# meld_all_non_inv.net
KiCad netlist of a schematic drawn in EAGLE
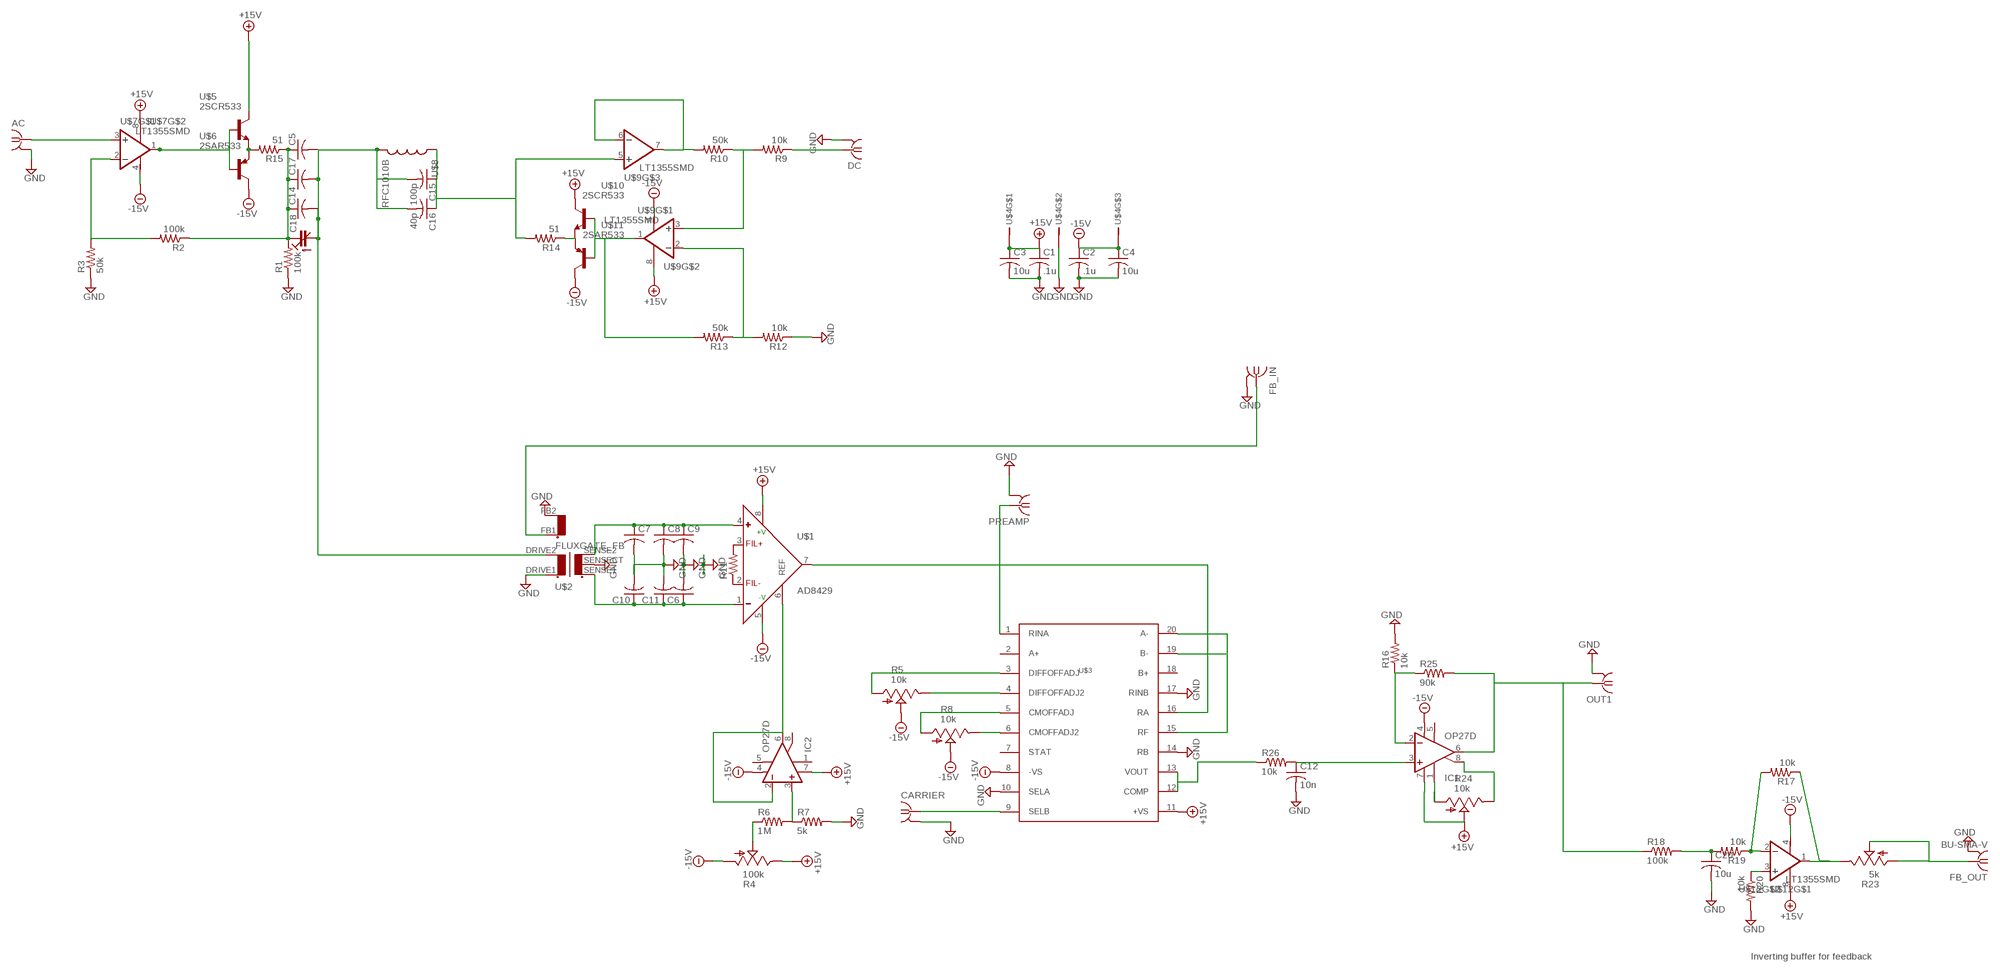
[diagram p0: schematic, sheet 1]

(export (version "E")
  (design (tool "Eeschema 10.0.6"))
  (components
    (comp (ref "AC")
      (value "SMA-142-0701-851/861")
      (footprint "eagle-import:J502-ND-142-0701-851_861")
      (fields (field (name "MF") "JOHNSON COMPONENTS") (field (name "MPN") "142-0701-851"))
      (libsource (lib "eagle-import") (part "SMA-142-0701-851/861"))
    )
    (comp (ref "C1")
      (value ".1u")
      (footprint "eagle-import:C1206")
      (libsource (lib "eagle-import") (part "C-USC1206"))
    )
    (comp (ref "C2")
      (value ".1u")
      (footprint "eagle-import:C1206")
      (libsource (lib "eagle-import") (part "C-USC1206"))
    )
    (comp (ref "C3")
      (value "10u")
      (footprint "eagle-import:C1206")
      (libsource (lib "eagle-import") (part "C-USC1206"))
    )
    (comp (ref "C4")
      (value "10u")
      (footprint "eagle-import:C1206")
      (libsource (lib "eagle-import") (part "C-USC1206"))
    )
    (comp (ref "C5")
      (value "C-USC0805")
      (footprint "eagle-import:C0805")
      (libsource (lib "eagle-import") (part "C-USC0805"))
    )
    (comp (ref "C6")
      (value "C-USC0805")
      (footprint "eagle-import:C0805")
      (libsource (lib "eagle-import") (part "C-USC0805"))
    )
    (comp (ref "C7")
      (value "C-USC0805")
      (footprint "eagle-import:C0805")
      (libsource (lib "eagle-import") (part "C-USC0805"))
    )
    (comp (ref "C8")
      (value "C-USC0805")
      (footprint "eagle-import:C0805")
      (libsource (lib "eagle-import") (part "C-USC0805"))
    )
    (comp (ref "C9")
      (value "C-USC0805")
      (footprint "eagle-import:C0805")
      (libsource (lib "eagle-import") (part "C-USC0805"))
    )
    (comp (ref "C10")
      (value "C-USC0805")
      (footprint "eagle-import:C0805")
      (libsource (lib "eagle-import") (part "C-USC0805"))
    )
    (comp (ref "C11")
      (value "C-USC0805")
      (footprint "eagle-import:C0805")
      (libsource (lib "eagle-import") (part "C-USC0805"))
    )
    (comp (ref "C12")
      (value "10n")
      (footprint "eagle-import:C0805")
      (libsource (lib "eagle-import") (part "C-USC0805"))
    )
    (comp (ref "C14")
      (value "C-USC0805")
      (footprint "eagle-import:C0805")
      (libsource (lib "eagle-import") (part "C-USC0805"))
    )
    (comp (ref "C15")
      (value "100p")
      (footprint "eagle-import:C0805")
      (libsource (lib "eagle-import") (part "C-USC0805"))
    )
    (comp (ref "C16")
      (value "40p")
      (footprint "eagle-import:C0805")
      (libsource (lib "eagle-import") (part "C-USC0805"))
    )
    (comp (ref "C17")
      (value "C-USC0805")
      (footprint "eagle-import:C0805")
      (libsource (lib "eagle-import") (part "C-USC0805"))
    )
    (comp (ref "C18")
      (value "C-TRIMM")
      (footprint "eagle-import:SGC3S")
      (libsource (lib "eagle-import") (part "C-TRIMM"))
    )
    (comp (ref "C20")
      (value "10u")
      (footprint "eagle-import:C1206")
      (libsource (lib "eagle-import") (part "C-USC1206"))
    )
    (comp (ref "CARRIER")
      (value "SMA-142-0701-851/861")
      (footprint "eagle-import:J502-ND-142-0701-851_861")
      (fields (field (name "MF") "JOHNSON COMPONENTS") (field (name "MPN") "142-0701-851"))
      (libsource (lib "eagle-import") (part "SMA-142-0701-851/861"))
    )
    (comp (ref "DC")
      (value "SMA-142-0701-851/861")
      (footprint "eagle-import:J502-ND-142-0701-851_861")
      (fields (field (name "MF") "JOHNSON COMPONENTS") (field (name "MPN") "142-0701-851"))
      (libsource (lib "eagle-import") (part "SMA-142-0701-851/861"))
    )
    (comp (ref "FB_IN")
      (value "SMA-142-0701-851/861")
      (footprint "eagle-import:J502-ND-142-0701-851_861")
      (fields (field (name "MF") "JOHNSON COMPONENTS") (field (name "MPN") "142-0701-851"))
      (libsource (lib "eagle-import") (part "SMA-142-0701-851/861"))
    )
    (comp (ref "FB_OUT")
      (value "BU-SMA-V")
      (footprint "eagle-import:BU-SMA-V")
      (libsource (lib "eagle-import") (part "BU-SMA-V"))
    )
    (comp (ref "IC1")
      (value "OP27D")
      (footprint "eagle-import:SO08")
      (libsource (lib "eagle-import") (part "OP27D"))
    )
    (comp (ref "IC2")
      (value "OP27D")
      (footprint "eagle-import:SO08")
      (libsource (lib "eagle-import") (part "OP27D"))
    )
    (comp (ref "OUT1")
      (value "SMA-142-0701-851/861")
      (footprint "eagle-import:J502-ND-142-0701-851_861")
      (fields (field (name "MF") "JOHNSON COMPONENTS") (field (name "MPN") "142-0701-851"))
      (libsource (lib "eagle-import") (part "SMA-142-0701-851/861"))
    )
    (comp (ref "PREAMP")
      (value "SMA-142-0701-851/861")
      (footprint "eagle-import:J502-ND-142-0701-851_861")
      (fields (field (name "MF") "JOHNSON COMPONENTS") (field (name "MPN") "142-0701-851"))
      (libsource (lib "eagle-import") (part "SMA-142-0701-851/861"))
    )
    (comp (ref "R1")
      (value "100k")
      (footprint "eagle-import:R0805")
      (libsource (lib "eagle-import") (part "R-US_R0805"))
    )
    (comp (ref "R2")
      (value "100k")
      (footprint "eagle-import:R0805")
      (libsource (lib "eagle-import") (part "R-US_R0805"))
    )
    (comp (ref "R3")
      (value "50k")
      (footprint "eagle-import:R0805")
      (libsource (lib "eagle-import") (part "R-US_R0805"))
    )
    (comp (ref "R4")
      (value "100k")
      (footprint "eagle-import:B64Y")
      (libsource (lib "eagle-import") (part "TRIM_US-B64Y"))
    )
    (comp (ref "R5")
      (value "10k")
      (footprint "eagle-import:B64Y")
      (libsource (lib "eagle-import") (part "TRIM_US-B64Y"))
    )
    (comp (ref "R6")
      (value "1M")
      (footprint "eagle-import:R0805")
      (libsource (lib "eagle-import") (part "R-US_R0805"))
    )
    (comp (ref "R7")
      (value "5k")
      (footprint "eagle-import:R0805")
      (libsource (lib "eagle-import") (part "R-US_R0805"))
    )
    (comp (ref "R8")
      (value "10k")
      (footprint "eagle-import:B64Y")
      (libsource (lib "eagle-import") (part "TRIM_US-B64Y"))
    )
    (comp (ref "R9")
      (value "10k")
      (footprint "eagle-import:R0805")
      (libsource (lib "eagle-import") (part "R-US_R0805"))
    )
    (comp (ref "R10")
      (value "50k")
      (footprint "eagle-import:R0805")
      (libsource (lib "eagle-import") (part "R-US_R0805"))
    )
    (comp (ref "R11")
      (value "R-US_R0805")
      (footprint "eagle-import:R0805")
      (libsource (lib "eagle-import") (part "R-US_R0805"))
    )
    (comp (ref "R12")
      (value "10k")
      (footprint "eagle-import:R0805")
      (libsource (lib "eagle-import") (part "R-US_R0805"))
    )
    (comp (ref "R13")
      (value "50k")
      (footprint "eagle-import:R0805")
      (libsource (lib "eagle-import") (part "R-US_R0805"))
    )
    (comp (ref "R14")
      (value "51")
      (footprint "eagle-import:R2512")
      (libsource (lib "eagle-import") (part "R-US_R2512"))
    )
    (comp (ref "R15")
      (value "51")
      (footprint "eagle-import:R2512")
      (libsource (lib "eagle-import") (part "R-US_R2512"))
    )
    (comp (ref "R16")
      (value "10k")
      (footprint "eagle-import:R0805")
      (libsource (lib "eagle-import") (part "resistor_R-US_R0805"))
    )
    (comp (ref "R17")
      (value "10k")
      (footprint "eagle-import:R0805")
      (libsource (lib "eagle-import") (part "resistor_R-US_R0805"))
    )
    (comp (ref "R18")
      (value "100k")
      (footprint "eagle-import:R0805")
      (libsource (lib "eagle-import") (part "resistor_R-US_R0805"))
    )
    (comp (ref "R19")
      (value "10k")
      (footprint "eagle-import:R0805")
      (libsource (lib "eagle-import") (part "resistor_R-US_R0805"))
    )
    (comp (ref "R20")
      (value "10k")
      (footprint "eagle-import:R0805")
      (libsource (lib "eagle-import") (part "resistor_R-US_R0805"))
    )
    (comp (ref "R23")
      (value "5k")
      (footprint "eagle-import:B64Y")
      (libsource (lib "eagle-import") (part "TRIM_US-B64Y"))
    )
    (comp (ref "R24")
      (value "10k")
      (footprint "eagle-import:B64Y")
      (libsource (lib "eagle-import") (part "TRIM_US-B64Y"))
    )
    (comp (ref "R25")
      (value "90k")
      (footprint "eagle-import:R0805")
      (libsource (lib "eagle-import") (part "resistor_R-US_R0805"))
    )
    (comp (ref "R26")
      (value "10k")
      (footprint "eagle-import:R0805")
      (libsource (lib "eagle-import") (part "resistor_R-US_R0805"))
    )
    (comp (ref "U$1")
      (value "AD8429")
      (footprint "eagle-import:SO8")
      (libsource (lib "eagle-import") (part "AD8428"))
    )
    (comp (ref "U$2")
      (value "FLUXGATE_FB")
      (footprint "eagle-import:PARA_FB")
      (libsource (lib "eagle-import") (part "FLUXGATE_FB"))
    )
    (comp (ref "U$3")
      (value "AD630")
      (footprint "eagle-import:SOIC20R")
      (libsource (lib "eagle-import") (part "AD630"))
    )
    (comp (ref "U$4")
      (value "B3B-AM")
      (footprint "eagle-import:B3B-AM")
      (libsource (lib "eagle-import") (part "B3B-AM"))
    )
    (comp (ref "U$5")
      (value "2SCR533")
      (footprint "eagle-import:SOT89-BCE")
      (libsource (lib "eagle-import") (part "2SCR533"))
    )
    (comp (ref "U$6")
      (value "2SAR533")
      (footprint "eagle-import:SOT89-BCE")
      (libsource (lib "eagle-import") (part "2SAR533"))
    )
    (comp (ref "U$7")
      (value "LT1355SMD")
      (footprint "eagle-import:SOIC8")
      (libsource (lib "eagle-import") (part "LT1355SMD"))
    )
    (comp (ref "U$8")
      (value "RFC1010B")
      (footprint "eagle-import:186KE")
      (libsource (lib "eagle-import") (part "RFC1010B"))
    )
    (comp (ref "U$9")
      (value "LT1355SMD")
      (footprint "eagle-import:SOIC8")
      (libsource (lib "eagle-import") (part "LT1355SMD"))
    )
    (comp (ref "U$10")
      (value "2SCR533")
      (footprint "eagle-import:SOT89-BCE")
      (libsource (lib "eagle-import") (part "2SCR533"))
    )
    (comp (ref "U$11")
      (value "2SAR533")
      (footprint "eagle-import:SOT89-BCE")
      (libsource (lib "eagle-import") (part "2SAR533"))
    )
    (comp (ref "U$12")
      (value "LT1355SMD")
      (footprint "eagle-import:SOIC8")
      (libsource (lib "eagle-import") (part "LT1355SMD"))
    )
  )
  (nets
    (net (code "1") (name "+15V") (class "Default")
      (node (ref "C1") (pin "1") (pinfunction "1_1") (pintype "passive"))
      (node (ref "C3") (pin "1") (pinfunction "1_1") (pintype "passive"))
      (node (ref "IC1") (pin "7") (pinfunction "V+_7") (pintype "power_in"))
      (node (ref "IC2") (pin "7") (pinfunction "V+_7") (pintype "power_in"))
      (node (ref "R24") (pin "S") (pinfunction "S_S") (pintype "passive"))
      (node (ref "R4") (pin "E") (pinfunction "E_E") (pintype "passive"))
      (node (ref "U$1") (pin "8") (pinfunction "+V_8") (pintype "power_in"))
      (node (ref "U$10") (pin "C") (pinfunction "C_C") (pintype "passive"))
      (node (ref "U$12") (pin "8") (pinfunction "V+_8") (pintype "power_in"))
      (node (ref "U$3") (pin "11") (pinfunction "+VS_11") (pintype "bidirectional"))
      (node (ref "U$4") (pin "1") (pinfunction "1_1") (pintype "passive"))
      (node (ref "U$5") (pin "C") (pinfunction "C_C") (pintype "passive"))
      (node (ref "U$7") (pin "8") (pinfunction "V+_8") (pintype "power_in"))
      (node (ref "U$9") (pin "8") (pinfunction "V+_8") (pintype "power_in"))
    )
    (net (code "2") (name "-15V") (class "Default")
      (node (ref "C2") (pin "1") (pinfunction "1_1") (pintype "passive"))
      (node (ref "C4") (pin "1") (pinfunction "1_1") (pintype "passive"))
      (node (ref "IC1") (pin "4") (pinfunction "V-_4") (pintype "power_in"))
      (node (ref "IC2") (pin "4") (pinfunction "V-_4") (pintype "power_in"))
      (node (ref "R4") (pin "A") (pinfunction "A_A") (pintype "passive"))
      (node (ref "R5") (pin "S") (pinfunction "S_S") (pintype "passive"))
      (node (ref "R8") (pin "S") (pinfunction "S_S") (pintype "passive"))
      (node (ref "U$1") (pin "5") (pinfunction "-V_5") (pintype "power_in"))
      (node (ref "U$11") (pin "C") (pinfunction "C_C") (pintype "passive"))
      (node (ref "U$12") (pin "4") (pinfunction "V-_4") (pintype "power_in"))
      (node (ref "U$3") (pin "8") (pinfunction "-VS_8") (pintype "bidirectional"))
      (node (ref "U$4") (pin "3") (pinfunction "1_3") (pintype "passive"))
      (node (ref "U$6") (pin "C") (pinfunction "C_C") (pintype "passive"))
      (node (ref "U$7") (pin "4") (pinfunction "V-_4") (pintype "power_in"))
      (node (ref "U$9") (pin "4") (pinfunction "V-_4") (pintype "power_in"))
    )
    (net (code "3") (name "GND") (class "Default")
      (node (ref "AC") (pin "G@1") (pinfunction "2_G@1") (pintype "passive"))
      (node (ref "AC") (pin "G@2") (pinfunction "2_G@2") (pintype "passive"))
      (node (ref "AC") (pin "G@3") (pinfunction "2_G@3") (pintype "passive"))
      (node (ref "AC") (pin "G@4") (pinfunction "2_G@4") (pintype "passive"))
      (node (ref "C1") (pin "2") (pinfunction "2_2") (pintype "passive"))
      (node (ref "C10") (pin "2") (pinfunction "2_2") (pintype "passive"))
      (node (ref "C11") (pin "2") (pinfunction "2_2") (pintype "passive"))
      (node (ref "C12") (pin "2") (pinfunction "2_2") (pintype "passive"))
      (node (ref "C2") (pin "2") (pinfunction "2_2") (pintype "passive"))
      (node (ref "C20") (pin "2") (pinfunction "2_2") (pintype "passive"))
      (node (ref "C3") (pin "2") (pinfunction "2_2") (pintype "passive"))
      (node (ref "C4") (pin "2") (pinfunction "2_2") (pintype "passive"))
      (node (ref "C6") (pin "2") (pinfunction "2_2") (pintype "passive"))
      (node (ref "C7") (pin "2") (pinfunction "2_2") (pintype "passive"))
      (node (ref "C8") (pin "2") (pinfunction "2_2") (pintype "passive"))
      (node (ref "C9") (pin "2") (pinfunction "2_2") (pintype "passive"))
      (node (ref "CARRIER") (pin "G@1") (pinfunction "2_G@1") (pintype "passive"))
      (node (ref "CARRIER") (pin "G@2") (pinfunction "2_G@2") (pintype "passive"))
      (node (ref "CARRIER") (pin "G@3") (pinfunction "2_G@3") (pintype "passive"))
      (node (ref "CARRIER") (pin "G@4") (pinfunction "2_G@4") (pintype "passive"))
      (node (ref "DC") (pin "G@1") (pinfunction "2_G@1") (pintype "passive"))
      (node (ref "DC") (pin "G@2") (pinfunction "2_G@2") (pintype "passive"))
      (node (ref "DC") (pin "G@3") (pinfunction "2_G@3") (pintype "passive"))
      (node (ref "DC") (pin "G@4") (pinfunction "2_G@4") (pintype "passive"))
      (node (ref "FB_IN") (pin "G@1") (pinfunction "2_G@1") (pintype "passive"))
      (node (ref "FB_IN") (pin "G@2") (pinfunction "2_G@2") (pintype "passive"))
      (node (ref "FB_IN") (pin "G@3") (pinfunction "2_G@3") (pintype "passive"))
      (node (ref "FB_IN") (pin "G@4") (pinfunction "2_G@4") (pintype "passive"))
      (node (ref "FB_OUT") (pin "2") (pinfunction "2_2") (pintype "passive"))
      (node (ref "FB_OUT") (pin "3") (pinfunction "2_3") (pintype "passive"))
      (node (ref "FB_OUT") (pin "4") (pinfunction "2_4") (pintype "passive"))
      (node (ref "FB_OUT") (pin "5") (pinfunction "2_5") (pintype "passive"))
      (node (ref "OUT1") (pin "G@1") (pinfunction "2_G@1") (pintype "passive"))
      (node (ref "OUT1") (pin "G@2") (pinfunction "2_G@2") (pintype "passive"))
      (node (ref "OUT1") (pin "G@3") (pinfunction "2_G@3") (pintype "passive"))
      (node (ref "OUT1") (pin "G@4") (pinfunction "2_G@4") (pintype "passive"))
      (node (ref "PREAMP") (pin "G@1") (pinfunction "2_G@1") (pintype "passive"))
      (node (ref "PREAMP") (pin "G@2") (pinfunction "2_G@2") (pintype "passive"))
      (node (ref "PREAMP") (pin "G@3") (pinfunction "2_G@3") (pintype "passive"))
      (node (ref "PREAMP") (pin "G@4") (pinfunction "2_G@4") (pintype "passive"))
      (node (ref "R1") (pin "1") (pinfunction "1_1") (pintype "passive"))
      (node (ref "R12") (pin "1") (pinfunction "1_1") (pintype "passive"))
      (node (ref "R16") (pin "2") (pinfunction "2_2") (pintype "passive"))
      (node (ref "R20") (pin "2") (pinfunction "2_2") (pintype "passive"))
      (node (ref "R3") (pin "1") (pinfunction "1_1") (pintype "passive"))
      (node (ref "R7") (pin "2") (pinfunction "2_2") (pintype "passive"))
      (node (ref "U$2") (pin "DRIVE1") (pinfunction "1_DRIVE1") (pintype "passive"))
      (node (ref "U$2") (pin "FB2") (pinfunction "7_FB2") (pintype "passive"))
      (node (ref "U$2") (pin "SENSECT") (pinfunction "4_SENSECT") (pintype "passive"))
      (node (ref "U$3") (pin "10") (pinfunction "SELA_10") (pintype "bidirectional"))
      (node (ref "U$3") (pin "14") (pinfunction "RB_14") (pintype "bidirectional"))
      (node (ref "U$3") (pin "17") (pinfunction "RINB_17") (pintype "bidirectional"))
      (node (ref "U$4") (pin "2") (pinfunction "1_2") (pintype "passive"))
    )
    (net (code "4") (name "Net-(C18-A)") (class "Default")
      (node (ref "C14") (pin "2") (pinfunction "2_2") (pintype "passive"))
      (node (ref "C15") (pin "2") (pinfunction "2_2") (pintype "passive"))
      (node (ref "C16") (pin "2") (pinfunction "2_2") (pintype "passive"))
      (node (ref "C17") (pin "2") (pinfunction "2_2") (pintype "passive"))
      (node (ref "C18") (pin "P$1") (pinfunction "A_P$1") (pintype "passive"))
      (node (ref "C5") (pin "2") (pinfunction "2_2") (pintype "passive"))
      (node (ref "U$2") (pin "DRIVE2") (pinfunction "2_DRIVE2") (pintype "passive"))
      (node (ref "U$8") (pin "P$2") (pinfunction "2_P$2") (pintype "passive"))
    )
    (net (code "5") (name "Net-(C18-E)") (class "Default")
      (node (ref "C14") (pin "1") (pinfunction "1_1") (pintype "passive"))
      (node (ref "C17") (pin "1") (pinfunction "1_1") (pintype "passive"))
      (node (ref "C18") (pin "P$2") (pinfunction "E_P$2") (pintype "passive"))
      (node (ref "C5") (pin "1") (pinfunction "1_1") (pintype "passive"))
      (node (ref "R1") (pin "2") (pinfunction "2_2") (pintype "passive"))
      (node (ref "R15") (pin "1") (pinfunction "1_1") (pintype "passive"))
      (node (ref "R2") (pin "1") (pinfunction "1_1") (pintype "passive"))
    )
    (net (code "6") (name "Net-(C20-Pad1)") (class "Default")
      (node (ref "C20") (pin "1") (pinfunction "1_1") (pintype "passive"))
      (node (ref "R18") (pin "2") (pinfunction "2_2") (pintype "passive"))
      (node (ref "R19") (pin "2") (pinfunction "2_2") (pintype "passive"))
    )
    (net (code "7") (name "Net-(DC-Pad1)") (class "Default")
      (node (ref "DC") (pin "1") (pinfunction "1_1") (pintype "passive"))
      (node (ref "R9") (pin "1") (pinfunction "1_1") (pintype "passive"))
    )
    (net (code "8") (name "Net-(FB_OUT-Pad1)") (class "Default")
      (node (ref "FB_OUT") (pin "1") (pinfunction "1_1") (pintype "passive"))
      (node (ref "R23") (pin "A") (pinfunction "A_A") (pintype "passive"))
      (node (ref "R23") (pin "S") (pinfunction "S_S") (pintype "passive"))
    )
    (net (code "9") (name "Net-(IC1-+IN)") (class "Default")
      (node (ref "C12") (pin "1") (pinfunction "1_1") (pintype "passive"))
      (node (ref "IC1") (pin "3") (pinfunction "+IN_3") (pintype "input"))
      (node (ref "R26") (pin "2") (pinfunction "2_2") (pintype "passive"))
    )
    (net (code "10") (name "Net-(IC1--IN)") (class "Default")
      (node (ref "IC1") (pin "2") (pinfunction "-IN_2") (pintype "input"))
      (node (ref "R16") (pin "1") (pinfunction "1_1") (pintype "passive"))
      (node (ref "R25") (pin "1") (pinfunction "1_1") (pintype "passive"))
    )
    (net (code "11") (name "Net-(IC1-ON1)") (class "Default")
      (node (ref "IC1") (pin "1") (pinfunction "ON1_1") (pintype "passive"))
      (node (ref "R24") (pin "A") (pinfunction "A_A") (pintype "passive"))
    )
    (net (code "12") (name "Net-(IC1-ON2)") (class "Default")
      (node (ref "IC1") (pin "8") (pinfunction "ON2_8") (pintype "passive"))
      (node (ref "R24") (pin "E") (pinfunction "E_E") (pintype "passive"))
    )
    (net (code "13") (name "Net-(IC1-OUT)") (class "Default")
      (node (ref "IC1") (pin "6") (pinfunction "OUT_6") (pintype "output"))
      (node (ref "OUT1") (pin "1") (pinfunction "1_1") (pintype "passive"))
      (node (ref "R18") (pin "1") (pinfunction "1_1") (pintype "passive"))
      (node (ref "R25") (pin "2") (pinfunction "2_2") (pintype "passive"))
    )
    (net (code "14") (name "Net-(IC2-+IN)") (class "Default")
      (node (ref "IC2") (pin "3") (pinfunction "+IN_3") (pintype "input"))
      (node (ref "R6") (pin "2") (pinfunction "2_2") (pintype "passive"))
      (node (ref "R7") (pin "1") (pinfunction "1_1") (pintype "passive"))
    )
    (net (code "15") (name "Net-(IC2--IN)") (class "Default")
      (node (ref "IC2") (pin "2") (pinfunction "-IN_2") (pintype "input"))
      (node (ref "IC2") (pin "6") (pinfunction "OUT_6") (pintype "output"))
      (node (ref "U$1") (pin "6") (pinfunction "REF_6") (pintype "passive"))
    )
    (net (code "16") (name "Net-(R4-PadS)") (class "Default")
      (node (ref "R4") (pin "S") (pinfunction "S_S") (pintype "passive"))
      (node (ref "R6") (pin "1") (pinfunction "1_1") (pintype "passive"))
    )
    (net (code "17") (name "Net-(R14-Pad1)") (class "Default")
      (node (ref "R14") (pin "1") (pinfunction "1_1") (pintype "passive"))
      (node (ref "U$10") (pin "E") (pinfunction "E_E") (pintype "passive"))
      (node (ref "U$11") (pin "E") (pinfunction "E_E") (pintype "passive"))
    )
    (net (code "18") (name "Net-(R15-Pad2)") (class "Default")
      (node (ref "R15") (pin "2") (pinfunction "2_2") (pintype "passive"))
      (node (ref "U$5") (pin "E") (pinfunction "E_E") (pintype "passive"))
      (node (ref "U$6") (pin "E") (pinfunction "E_E") (pintype "passive"))
    )
    (net (code "19") (name "Net-(U$1-+)") (class "Default")
      (node (ref "C7") (pin "1") (pinfunction "1_1") (pintype "passive"))
      (node (ref "C8") (pin "1") (pinfunction "1_1") (pintype "passive"))
      (node (ref "C9") (pin "1") (pinfunction "1_1") (pintype "passive"))
      (node (ref "U$1") (pin "4") (pinfunction "+_4") (pintype "input"))
      (node (ref "U$2") (pin "SENSE2") (pinfunction "3_SENSE2") (pintype "passive"))
    )
    (net (code "20") (name "Net-(U$1--)") (class "Default")
      (node (ref "C10") (pin "1") (pinfunction "1_1") (pintype "passive"))
      (node (ref "C11") (pin "1") (pinfunction "1_1") (pintype "passive"))
      (node (ref "C6") (pin "1") (pinfunction "1_1") (pintype "passive"))
      (node (ref "U$1") (pin "1") (pinfunction "-_1") (pintype "input"))
      (node (ref "U$2") (pin "SENSE1") (pinfunction "5_SENSE1") (pintype "passive"))
    )
    (net (code "21") (name "Net-(U$1-FIL+)") (class "Default")
      (node (ref "R11") (pin "2") (pinfunction "2_2") (pintype "passive"))
      (node (ref "U$1") (pin "3") (pinfunction "FIL+_3") (pintype "passive"))
    )
    (net (code "22") (name "Net-(U$1-FIL-)") (class "Default")
      (node (ref "R11") (pin "1") (pinfunction "1_1") (pintype "passive"))
      (node (ref "U$1") (pin "2") (pinfunction "FIL-_2") (pintype "passive"))
    )
    (net (code "23") (name "Net-(U$1-OUT)") (class "Default")
      (node (ref "PREAMP") (pin "1") (pinfunction "1_1") (pintype "passive"))
      (node (ref "U$1") (pin "7") (pinfunction "OUT_7") (pintype "output"))
      (node (ref "U$3") (pin "1") (pinfunction "RINA_1") (pintype "bidirectional"))
      (node (ref "U$3") (pin "16") (pinfunction "RA_16") (pintype "bidirectional"))
    )
    (net (code "24") (name "Net-(U$2-6)") (class "Default")
      (node (ref "FB_IN") (pin "1") (pinfunction "1_1") (pintype "passive"))
      (node (ref "U$2") (pin "FB1") (pinfunction "6_FB1") (pintype "passive"))
    )
    (net (code "25") (name "Net-(U$3-A-)") (class "Default")
      (node (ref "U$3") (pin "15") (pinfunction "RF_15") (pintype "bidirectional"))
      (node (ref "U$3") (pin "19") (pinfunction "B-_19") (pintype "bidirectional"))
      (node (ref "U$3") (pin "20") (pinfunction "A-_20") (pintype "bidirectional"))
    )
    (net (code "26") (name "Net-(U$3-CMOFFADJ)") (class "Default")
      (node (ref "R8") (pin "A") (pinfunction "A_A") (pintype "passive"))
      (node (ref "U$3") (pin "5") (pinfunction "CMOFFADJ_5") (pintype "bidirectional"))
    )
    (net (code "27") (name "Net-(U$3-CMOFFADJ2)") (class "Default")
      (node (ref "R8") (pin "E") (pinfunction "E_E") (pintype "passive"))
      (node (ref "U$3") (pin "6") (pinfunction "CMOFFADJ2_6") (pintype "bidirectional"))
    )
    (net (code "28") (name "Net-(U$3-COMP)") (class "Default")
      (node (ref "R26") (pin "1") (pinfunction "1_1") (pintype "passive"))
      (node (ref "U$3") (pin "12") (pinfunction "COMP_12") (pintype "bidirectional"))
      (node (ref "U$3") (pin "13") (pinfunction "VOUT_13") (pintype "bidirectional"))
    )
    (net (code "29") (name "Net-(U$3-DIFFOFFADJ)") (class "Default")
      (node (ref "R5") (pin "A") (pinfunction "A_A") (pintype "passive"))
      (node (ref "U$3") (pin "3") (pinfunction "DIFFOFFADJ_3") (pintype "bidirectional"))
    )
    (net (code "30") (name "Net-(U$3-DIFFOFFADJ2)") (class "Default")
      (node (ref "R5") (pin "E") (pinfunction "E_E") (pintype "passive"))
      (node (ref "U$3") (pin "4") (pinfunction "DIFFOFFADJ2_4") (pintype "bidirectional"))
    )
    (net (code "31") (name "Net-(U$3-SELB)") (class "Default")
      (node (ref "CARRIER") (pin "1") (pinfunction "1_1") (pintype "passive"))
      (node (ref "U$3") (pin "9") (pinfunction "SELB_9") (pintype "bidirectional"))
    )
    (net (code "32") (name "Net-(U$7A-+IN)") (class "Default")
      (node (ref "AC") (pin "1") (pinfunction "1_1") (pintype "passive"))
      (node (ref "U$7") (pin "3") (pinfunction "+IN_3") (pintype "input"))
    )
    (net (code "33") (name "Net-(U$7A--IN)") (class "Default")
      (node (ref "R2") (pin "2") (pinfunction "2_2") (pintype "passive"))
      (node (ref "R3") (pin "2") (pinfunction "2_2") (pintype "passive"))
      (node (ref "U$7") (pin "2") (pinfunction "-IN_2") (pintype "input"))
    )
    (net (code "34") (name "Net-(U$7A-OUT)") (class "Default")
      (node (ref "U$5") (pin "B") (pinfunction "B_B") (pintype "passive"))
      (node (ref "U$6") (pin "B") (pinfunction "B_B") (pintype "passive"))
      (node (ref "U$7") (pin "1") (pinfunction "OUT_1") (pintype "output"))
    )
    (net (code "35") (name "Net-(U$8-1)") (class "Default")
      (node (ref "C15") (pin "1") (pinfunction "1_1") (pintype "passive"))
      (node (ref "C16") (pin "1") (pinfunction "1_1") (pintype "passive"))
      (node (ref "R14") (pin "2") (pinfunction "2_2") (pintype "passive"))
      (node (ref "U$8") (pin "P$1") (pinfunction "1_P$1") (pintype "passive"))
      (node (ref "U$9") (pin "5") (pinfunction "+IN_5") (pintype "input"))
    )
    (net (code "36") (name "Net-(U$9A-+IN)") (class "Default")
      (node (ref "R10") (pin "1") (pinfunction "1_1") (pintype "passive"))
      (node (ref "R9") (pin "2") (pinfunction "2_2") (pintype "passive"))
      (node (ref "U$9") (pin "3") (pinfunction "+IN_3") (pintype "input"))
    )
    (net (code "37") (name "Net-(U$9A--IN)") (class "Default")
      (node (ref "R12") (pin "2") (pinfunction "2_2") (pintype "passive"))
      (node (ref "R13") (pin "1") (pinfunction "1_1") (pintype "passive"))
      (node (ref "U$9") (pin "2") (pinfunction "-IN_2") (pintype "input"))
    )
    (net (code "38") (name "Net-(U$9A-OUT)") (class "Default")
      (node (ref "R13") (pin "2") (pinfunction "2_2") (pintype "passive"))
      (node (ref "U$10") (pin "B") (pinfunction "B_B") (pintype "passive"))
      (node (ref "U$11") (pin "B") (pinfunction "B_B") (pintype "passive"))
      (node (ref "U$9") (pin "1") (pinfunction "OUT_1") (pintype "output"))
    )
    (net (code "39") (name "Net-(U$9C--IN)") (class "Default")
      (node (ref "R10") (pin "2") (pinfunction "2_2") (pintype "passive"))
      (node (ref "U$9") (pin "6") (pinfunction "-IN_6") (pintype "input"))
      (node (ref "U$9") (pin "7") (pinfunction "OUT_7") (pintype "output"))
    )
    (net (code "40") (name "Net-(U$12A-+IN)") (class "Default")
      (node (ref "R20") (pin "1") (pinfunction "1_1") (pintype "passive"))
      (node (ref "U$12") (pin "3") (pinfunction "+IN_3") (pintype "input"))
    )
    (net (code "41") (name "Net-(U$12A--IN)") (class "Default")
      (node (ref "R17") (pin "2") (pinfunction "2_2") (pintype "passive"))
      (node (ref "R19") (pin "1") (pinfunction "1_1") (pintype "passive"))
      (node (ref "U$12") (pin "2") (pinfunction "-IN_2") (pintype "input"))
    )
    (net (code "42") (name "Net-(U$12A-OUT)") (class "Default")
      (node (ref "R17") (pin "1") (pinfunction "1_1") (pintype "passive"))
      (node (ref "R23") (pin "E") (pinfunction "E_E") (pintype "passive"))
      (node (ref "U$12") (pin "1") (pinfunction "OUT_1") (pintype "output"))
    )
    (net (code "43") (name "unconnected-(IC1-OPT-Pad5)") (class "Default")
      (node (ref "IC1") (pin "5") (pinfunction "OPT_5") (pintype "passive"))
    )
    (net (code "44") (name "unconnected-(IC2-ON1-Pad1)") (class "Default")
      (node (ref "IC2") (pin "1") (pinfunction "ON1_1") (pintype "passive"))
    )
    (net (code "45") (name "unconnected-(IC2-ON2-Pad8)") (class "Default")
      (node (ref "IC2") (pin "8") (pinfunction "ON2_8") (pintype "passive"))
    )
    (net (code "46") (name "unconnected-(IC2-OPT-Pad5)") (class "Default")
      (node (ref "IC2") (pin "5") (pinfunction "OPT_5") (pintype "passive"))
    )
    (net (code "47") (name "unconnected-(U$3-A+-Pad2)") (class "Default")
      (node (ref "U$3") (pin "2") (pinfunction "A+_2") (pintype "bidirectional"))
    )
    (net (code "48") (name "unconnected-(U$3-B+-Pad18)") (class "Default")
      (node (ref "U$3") (pin "18") (pinfunction "B+_18") (pintype "bidirectional"))
    )
    (net (code "49") (name "unconnected-(U$3-STAT-Pad7)") (class "Default")
      (node (ref "U$3") (pin "7") (pinfunction "STAT_7") (pintype "bidirectional"))
    )
  )
)
